# Chocolate_Vending_Machine_V2_1.net
KiCad netlist of a schematic drawn in Altium Designer
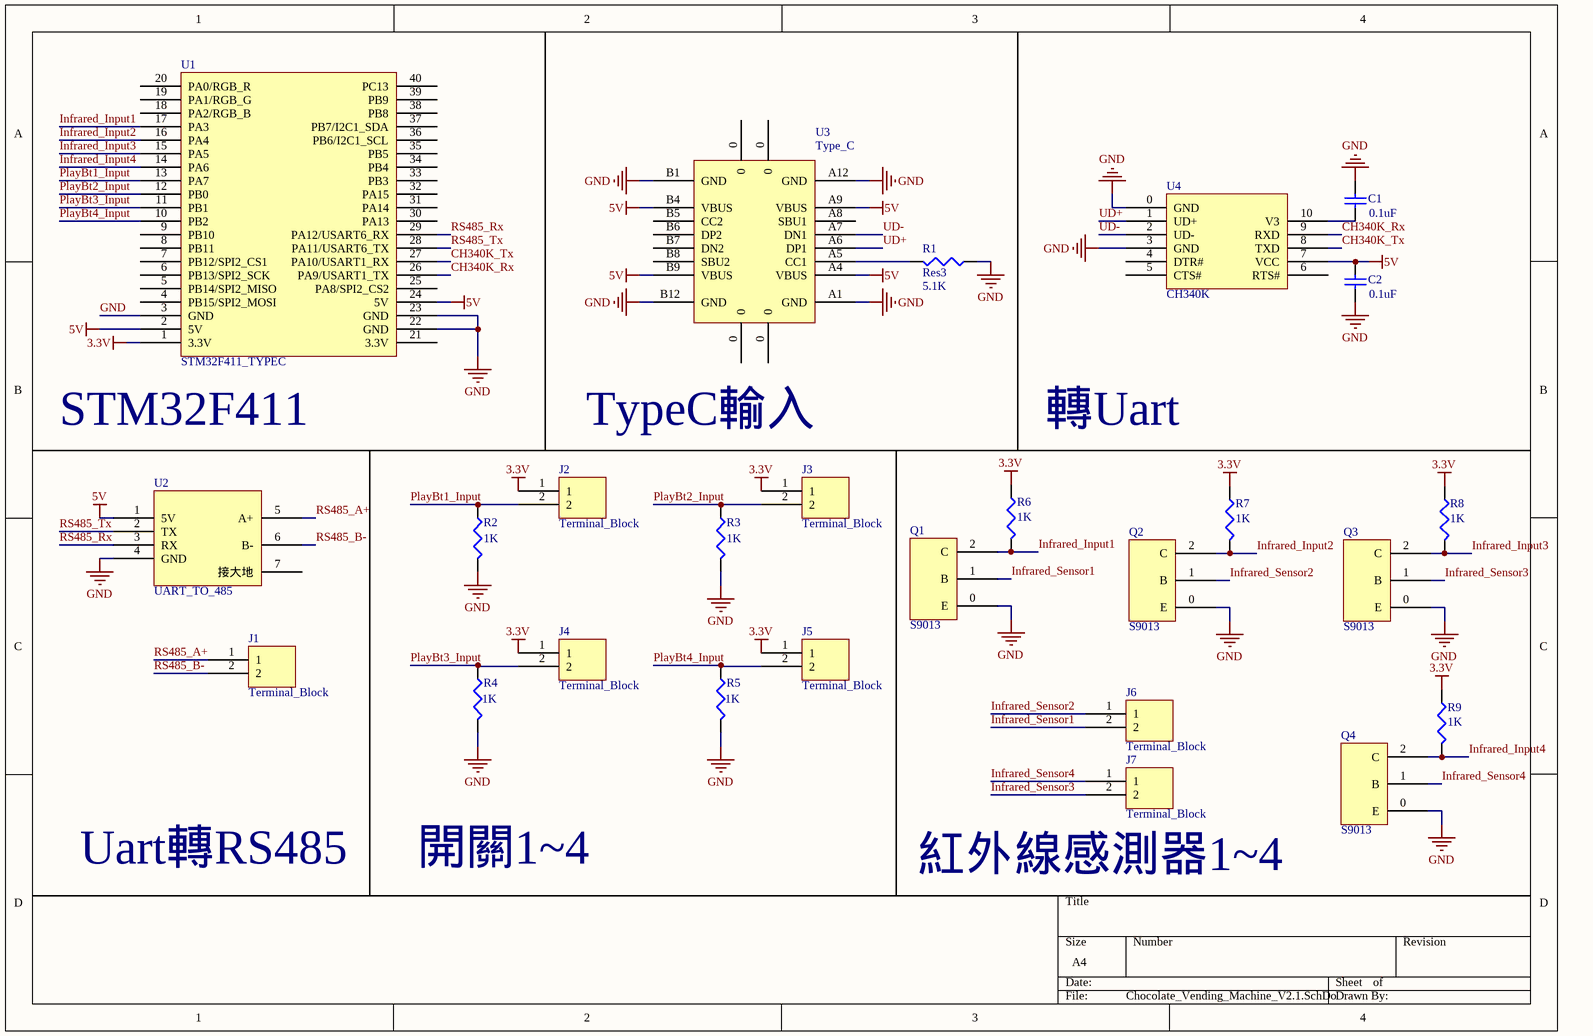
[diagram p0: Chocolate_Vending_Machine_V2.1.SchDoc]

(export (version "E")
  (design (tool "Eeschema 10.0.6"))
  (components
    (comp (ref "C1")
      (value "0.1uF")
      (footprint "1608[0603]")
      (description "Capacitor (Semiconductor SIM Model)")
      (fields (field (name "Comment") "Cap Semi") (field (name "PUBLISHER") "Altium Limited"))
      (libsource (lib "Miscellaneous Devices") (part "Cap Semi"))
    )
    (comp (ref "C2")
      (value "0.1uF")
      (footprint "1608[0603]")
      (description "Capacitor (Semiconductor SIM Model)")
      (fields (field (name "Comment") "Cap Semi") (field (name "PUBLISHER") "Altium Limited"))
      (libsource (lib "Miscellaneous Devices") (part "Cap Semi"))
    )
    (comp (ref "J1")
      (value "Terminal_Block")
      (footprint "terminal block")
      (libsource (lib "Lab_share") (part "Terminal Block"))
    )
    (comp (ref "J2")
      (value "Terminal_Block")
      (footprint "terminal block")
      (libsource (lib "Lab_share") (part "Terminal Block"))
    )
    (comp (ref "J3")
      (value "Terminal_Block")
      (footprint "terminal block")
      (libsource (lib "Lab_share") (part "Terminal Block"))
    )
    (comp (ref "J4")
      (value "Terminal_Block")
      (footprint "terminal block")
      (libsource (lib "Lab_share") (part "Terminal Block"))
    )
    (comp (ref "J5")
      (value "Terminal_Block")
      (footprint "terminal block")
      (libsource (lib "Lab_share") (part "Terminal Block"))
    )
    (comp (ref "J6")
      (value "Terminal_Block")
      (footprint "terminal block")
      (libsource (lib "Lab_share") (part "Terminal Block"))
    )
    (comp (ref "J7")
      (value "Terminal_Block")
      (footprint "terminal block")
      (libsource (lib "Lab_share") (part "Terminal Block"))
    )
    (comp (ref "Q1") (value "S9013") (footprint "S9013") (libsource (lib "Lab_share") (part "S9013")))
    (comp (ref "Q2") (value "S9013") (footprint "S9013") (libsource (lib "Lab_share") (part "S9013")))
    (comp (ref "Q3") (value "S9013") (footprint "S9013") (libsource (lib "Lab_share") (part "S9013")))
    (comp (ref "Q4") (value "S9013") (footprint "S9013") (libsource (lib "Lab_share") (part "S9013")))
    (comp (ref "R1")
      (value "Res3")
      (footprint "J1-0603")
      (description "Resistor")
      (fields (field (name "ALTIUM_VALUE") "5.1K") (field (name "PUBLISHER") "Altium Limited"))
      (libsource (lib "Miscellaneous Devices") (part "Res3"))
    )
    (comp (ref "R2")
      (value "1K")
      (footprint "J1-0603")
      (description "Resistor")
      (fields (field (name "Comment") "Res3") (field (name "PUBLISHER") "Altium Limited"))
      (libsource (lib "Miscellaneous Devices") (part "Res3"))
    )
    (comp (ref "R3")
      (value "1K")
      (footprint "J1-0603")
      (description "Resistor")
      (fields (field (name "Comment") "Res3") (field (name "PUBLISHER") "Altium Limited"))
      (libsource (lib "Miscellaneous Devices") (part "Res3"))
    )
    (comp (ref "R4")
      (value "1K")
      (footprint "J1-0603")
      (description "Resistor")
      (fields (field (name "Comment") "Res3") (field (name "PUBLISHER") "Altium Limited"))
      (libsource (lib "Miscellaneous Devices") (part "Res3"))
    )
    (comp (ref "R5")
      (value "1K")
      (footprint "J1-0603")
      (description "Resistor")
      (fields (field (name "Comment") "Res3") (field (name "PUBLISHER") "Altium Limited"))
      (libsource (lib "Miscellaneous Devices") (part "Res3"))
    )
    (comp (ref "R6")
      (value "1K")
      (footprint "J1-0603")
      (description "Resistor")
      (fields (field (name "Comment") "Res3") (field (name "PUBLISHER") "Altium Limited"))
      (libsource (lib "Miscellaneous Devices") (part "Res3"))
    )
    (comp (ref "R7")
      (value "1K")
      (footprint "J1-0603")
      (description "Resistor")
      (fields (field (name "Comment") "Res3") (field (name "PUBLISHER") "Altium Limited"))
      (libsource (lib "Miscellaneous Devices") (part "Res3"))
    )
    (comp (ref "R8")
      (value "1K")
      (footprint "J1-0603")
      (description "Resistor")
      (fields (field (name "Comment") "Res3") (field (name "PUBLISHER") "Altium Limited"))
      (libsource (lib "Miscellaneous Devices") (part "Res3"))
    )
    (comp (ref "R9")
      (value "1K")
      (footprint "J1-0603")
      (description "Resistor")
      (fields (field (name "Comment") "Res3") (field (name "PUBLISHER") "Altium Limited"))
      (libsource (lib "Miscellaneous Devices") (part "Res3"))
    )
    (comp (ref "U1")
      (value "STM32F411_TYPEC")
      (footprint "STM32F411_TypeC")
      (libsource (lib "Lab_share") (part "STM32F411_TYPEC"))
    )
    (comp (ref "U2")
      (value "UART_TO_485")
      (footprint "UART_TO_RS485")
      (libsource (lib "Lab_share") (part "UART_TO_485"))
    )
    (comp (ref "U3") (value "Type_C") (footprint "Type_C_V2") (libsource (lib "Lab_share") (part "Type_C")))
    (comp (ref "U4") (value "CH340K") (footprint "CH340K_V1") (libsource (lib "Lab_share") (part "CH340K")))
  )
  (nets
    (net (code "1") (name "/CH340K_Rx") (class "Default")
      (node (ref "U1") (pin "26") (pinfunction "PA9/USART1_TX_26") (pintype "passive"))
      (node (ref "U4") (pin "9") (pinfunction "RXD_9") (pintype "passive"))
    )
    (net (code "2") (name "/CH340K_Tx") (class "Default")
      (node (ref "U1") (pin "27") (pinfunction "PA10/USART1_RX_27") (pintype "passive"))
      (node (ref "U4") (pin "8") (pinfunction "TXD_8") (pintype "passive"))
    )
    (net (code "3") (name "/Infrared_Input1") (class "Default")
      (node (ref "Q1") (pin "2") (pinfunction "C_2") (pintype "passive"))
      (node (ref "R6") (pin "2") (pinfunction "2_2") (pintype "passive"))
      (node (ref "U1") (pin "17") (pinfunction "PA3_17") (pintype "passive"))
    )
    (net (code "4") (name "/Infrared_Input2") (class "Default")
      (node (ref "Q2") (pin "2") (pinfunction "C_2") (pintype "passive"))
      (node (ref "R7") (pin "2") (pinfunction "2_2") (pintype "passive"))
      (node (ref "U1") (pin "16") (pinfunction "PA4_16") (pintype "passive"))
    )
    (net (code "5") (name "/Infrared_Input3") (class "Default")
      (node (ref "Q3") (pin "2") (pinfunction "C_2") (pintype "passive"))
      (node (ref "R8") (pin "2") (pinfunction "2_2") (pintype "passive"))
      (node (ref "U1") (pin "15") (pinfunction "PA5_15") (pintype "passive"))
    )
    (net (code "6") (name "/Infrared_Input4") (class "Default")
      (node (ref "Q4") (pin "2") (pinfunction "C_2") (pintype "passive"))
      (node (ref "R9") (pin "2") (pinfunction "2_2") (pintype "passive"))
      (node (ref "U1") (pin "14") (pinfunction "PA6_14") (pintype "passive"))
    )
    (net (code "7") (name "/Infrared_Sensor1") (class "Default")
      (node (ref "J6") (pin "2") (pinfunction "2_2") (pintype "passive"))
      (node (ref "Q1") (pin "1") (pinfunction "B_1") (pintype "passive"))
    )
    (net (code "8") (name "/Infrared_Sensor2") (class "Default")
      (node (ref "J6") (pin "1") (pinfunction "1_1") (pintype "passive"))
      (node (ref "Q2") (pin "1") (pinfunction "B_1") (pintype "passive"))
    )
    (net (code "9") (name "/Infrared_Sensor3") (class "Default")
      (node (ref "J7") (pin "2") (pinfunction "2_2") (pintype "passive"))
      (node (ref "Q3") (pin "1") (pinfunction "B_1") (pintype "passive"))
    )
    (net (code "10") (name "/Infrared_Sensor4") (class "Default")
      (node (ref "J7") (pin "1") (pinfunction "1_1") (pintype "passive"))
      (node (ref "Q4") (pin "1") (pinfunction "B_1") (pintype "passive"))
    )
    (net (code "11") (name "/PlayBt1_Input") (class "Default")
      (node (ref "J2") (pin "2") (pinfunction "2_2") (pintype "passive"))
      (node (ref "R2") (pin "1") (pinfunction "1_1") (pintype "passive"))
      (node (ref "U1") (pin "13") (pinfunction "PA7_13") (pintype "passive"))
    )
    (net (code "12") (name "/PlayBt2_Input") (class "Default")
      (node (ref "J3") (pin "2") (pinfunction "2_2") (pintype "passive"))
      (node (ref "R3") (pin "1") (pinfunction "1_1") (pintype "passive"))
      (node (ref "U1") (pin "12") (pinfunction "PB0_12") (pintype "passive"))
    )
    (net (code "13") (name "/PlayBt3_Input") (class "Default")
      (node (ref "J4") (pin "2") (pinfunction "2_2") (pintype "passive"))
      (node (ref "R4") (pin "1") (pinfunction "1_1") (pintype "passive"))
      (node (ref "U1") (pin "11") (pinfunction "PB1_11") (pintype "passive"))
    )
    (net (code "14") (name "/PlayBt4_Input") (class "Default")
      (node (ref "J5") (pin "2") (pinfunction "2_2") (pintype "passive"))
      (node (ref "R5") (pin "1") (pinfunction "1_1") (pintype "passive"))
      (node (ref "U1") (pin "10") (pinfunction "PB2_10") (pintype "passive"))
    )
    (net (code "15") (name "/RS485_A+") (class "Default")
      (node (ref "J1") (pin "1") (pinfunction "1_1") (pintype "passive"))
      (node (ref "U2") (pin "5") (pinfunction "A+_5") (pintype "passive"))
    )
    (net (code "16") (name "/RS485_B-") (class "Default")
      (node (ref "J1") (pin "2") (pinfunction "2_2") (pintype "passive"))
      (node (ref "U2") (pin "6") (pinfunction "B-_6") (pintype "passive"))
    )
    (net (code "17") (name "/RS485_Rx") (class "Default")
      (node (ref "U1") (pin "29") (pinfunction "PA12/USART6_RX_29") (pintype "passive"))
      (node (ref "U2") (pin "3") (pinfunction "RX_3") (pintype "passive"))
    )
    (net (code "18") (name "/RS485_Tx") (class "Default")
      (node (ref "U1") (pin "28") (pinfunction "PA11/USART6_TX_28") (pintype "passive"))
      (node (ref "U2") (pin "2") (pinfunction "TX_2") (pintype "passive"))
    )
    (net (code "19") (name "/UD+") (class "Default")
      (node (ref "U3") (pin "A6") (pinfunction "DP1_A6") (pintype "passive"))
      (node (ref "U4") (pin "1") (pinfunction "UD+_1") (pintype "passive"))
    )
    (net (code "20") (name "/UD-") (class "Default")
      (node (ref "U3") (pin "A7") (pinfunction "DN1_A7") (pintype "passive"))
      (node (ref "U4") (pin "2") (pinfunction "UD-_2") (pintype "passive"))
    )
    (net (code "21") (name "3.3V") (class "Default")
      (node (ref "J2") (pin "1") (pinfunction "1_1") (pintype "passive"))
      (node (ref "J3") (pin "1") (pinfunction "1_1") (pintype "passive"))
      (node (ref "J4") (pin "1") (pinfunction "1_1") (pintype "passive"))
      (node (ref "J5") (pin "1") (pinfunction "1_1") (pintype "passive"))
      (node (ref "R6") (pin "1") (pinfunction "1_1") (pintype "passive"))
      (node (ref "R7") (pin "1") (pinfunction "1_1") (pintype "passive"))
      (node (ref "R8") (pin "1") (pinfunction "1_1") (pintype "passive"))
      (node (ref "R9") (pin "1") (pinfunction "1_1") (pintype "passive"))
      (node (ref "U1") (pin "1") (pinfunction "3.3V_1") (pintype "passive"))
    )
    (net (code "22") (name "5V") (class "Default")
      (node (ref "C2") (pin "2") (pinfunction "2_2") (pintype "passive"))
      (node (ref "U1") (pin "2") (pinfunction "5V_2") (pintype "passive"))
      (node (ref "U1") (pin "24") (pinfunction "5V_24") (pintype "passive"))
      (node (ref "U2") (pin "1") (pinfunction "5V_1") (pintype "passive"))
      (node (ref "U3") (pin "A4") (pinfunction "VBUS_A4") (pintype "passive"))
      (node (ref "U3") (pin "A9") (pinfunction "VBUS_A9") (pintype "passive"))
      (node (ref "U3") (pin "B4") (pinfunction "VBUS_B4") (pintype "passive"))
      (node (ref "U3") (pin "B9") (pinfunction "VBUS_B9") (pintype "passive"))
      (node (ref "U4") (pin "7") (pinfunction "VCC_7") (pintype "passive"))
    )
    (net (code "23") (name "GND") (class "Default")
      (node (ref "C1") (pin "2") (pinfunction "2_2") (pintype "passive"))
      (node (ref "C2") (pin "1") (pinfunction "1_1") (pintype "passive"))
      (node (ref "Q1") (pin "0") (pinfunction "E_0") (pintype "passive"))
      (node (ref "Q2") (pin "0") (pinfunction "E_0") (pintype "passive"))
      (node (ref "Q3") (pin "0") (pinfunction "E_0") (pintype "passive"))
      (node (ref "Q4") (pin "0") (pinfunction "E_0") (pintype "passive"))
      (node (ref "R1") (pin "1") (pinfunction "1_1") (pintype "passive"))
      (node (ref "R2") (pin "2") (pinfunction "2_2") (pintype "passive"))
      (node (ref "R3") (pin "2") (pinfunction "2_2") (pintype "passive"))
      (node (ref "R4") (pin "2") (pinfunction "2_2") (pintype "passive"))
      (node (ref "R5") (pin "2") (pinfunction "2_2") (pintype "passive"))
      (node (ref "U1") (pin "22") (pinfunction "GND_22") (pintype "passive"))
      (node (ref "U1") (pin "23") (pinfunction "GND_23") (pintype "passive"))
      (node (ref "U1") (pin "3") (pinfunction "GND_3") (pintype "passive"))
      (node (ref "U2") (pin "4") (pinfunction "GND_4") (pintype "passive"))
      (node (ref "U3") (pin "A1") (pinfunction "GND_A1") (pintype "passive"))
      (node (ref "U3") (pin "A12") (pinfunction "GND_A12") (pintype "passive"))
      (node (ref "U3") (pin "B1") (pinfunction "GND_B1") (pintype "passive"))
      (node (ref "U3") (pin "B12") (pinfunction "GND_B12") (pintype "passive"))
      (node (ref "U4") (pin "0") (pinfunction "GND_0") (pintype "passive"))
      (node (ref "U4") (pin "3") (pinfunction "GND_3") (pintype "passive"))
    )
    (net (code "24") (name "Net-(U3-CC1)") (class "Default")
      (node (ref "R1") (pin "2") (pinfunction "2_2") (pintype "passive"))
      (node (ref "U3") (pin "A5") (pinfunction "CC1_A5") (pintype "passive"))
    )
    (net (code "25") (name "Net-(U4-V3)") (class "Default")
      (node (ref "C1") (pin "1") (pinfunction "1_1") (pintype "passive"))
      (node (ref "U4") (pin "10") (pinfunction "V3_10") (pintype "passive"))
    )
    (net (code "26") (name "unconnected-(U1-3.3V-Pad21)") (class "Default")
      (node (ref "U1") (pin "21") (pinfunction "3.3V_21") (pintype "passive"))
    )
    (net (code "27") (name "unconnected-(U1-PA0{slash}RGB_R-Pad20)") (class "Default")
      (node (ref "U1") (pin "20") (pinfunction "PA0/RGB_R_20") (pintype "passive"))
    )
    (net (code "28") (name "unconnected-(U1-PA1{slash}RGB_G-Pad19)") (class "Default")
      (node (ref "U1") (pin "19") (pinfunction "PA1/RGB_G_19") (pintype "passive"))
    )
    (net (code "29") (name "unconnected-(U1-PA2{slash}RGB_B-Pad18)") (class "Default")
      (node (ref "U1") (pin "18") (pinfunction "PA2/RGB_B_18") (pintype "passive"))
    )
    (net (code "30") (name "unconnected-(U1-PA8{slash}SPI2_CS2-Pad25)") (class "Default")
      (node (ref "U1") (pin "25") (pinfunction "PA8/SPI2_CS2_25") (pintype "passive"))
    )
    (net (code "31") (name "unconnected-(U1-PA13-Pad30)") (class "Default")
      (node (ref "U1") (pin "30") (pinfunction "PA13_30") (pintype "passive"))
    )
    (net (code "32") (name "unconnected-(U1-PA14-Pad31)") (class "Default")
      (node (ref "U1") (pin "31") (pinfunction "PA14_31") (pintype "passive"))
    )
    (net (code "33") (name "unconnected-(U1-PA15-Pad32)") (class "Default")
      (node (ref "U1") (pin "32") (pinfunction "PA15_32") (pintype "passive"))
    )
    (net (code "34") (name "unconnected-(U1-PB3-Pad33)") (class "Default")
      (node (ref "U1") (pin "33") (pinfunction "PB3_33") (pintype "passive"))
    )
    (net (code "35") (name "unconnected-(U1-PB4-Pad34)") (class "Default")
      (node (ref "U1") (pin "34") (pinfunction "PB4_34") (pintype "passive"))
    )
    (net (code "36") (name "unconnected-(U1-PB5-Pad35)") (class "Default")
      (node (ref "U1") (pin "35") (pinfunction "PB5_35") (pintype "passive"))
    )
    (net (code "37") (name "unconnected-(U1-PB6{slash}I2C1_SCL-Pad36)") (class "Default")
      (node (ref "U1") (pin "36") (pinfunction "PB6/I2C1_SCL_36") (pintype "passive"))
    )
    (net (code "38") (name "unconnected-(U1-PB7{slash}I2C1_SDA-Pad37)") (class "Default")
      (node (ref "U1") (pin "37") (pinfunction "PB7/I2C1_SDA_37") (pintype "passive"))
    )
    (net (code "39") (name "unconnected-(U1-PB8-Pad38)") (class "Default")
      (node (ref "U1") (pin "38") (pinfunction "PB8_38") (pintype "passive"))
    )
    (net (code "40") (name "unconnected-(U1-PB9-Pad39)") (class "Default")
      (node (ref "U1") (pin "39") (pinfunction "PB9_39") (pintype "passive"))
    )
    (net (code "41") (name "unconnected-(U1-PB10-Pad9)") (class "Default")
      (node (ref "U1") (pin "9") (pinfunction "PB10_9") (pintype "passive"))
    )
    (net (code "42") (name "unconnected-(U1-PB11-Pad8)") (class "Default")
      (node (ref "U1") (pin "8") (pinfunction "PB11_8") (pintype "passive"))
    )
    (net (code "43") (name "unconnected-(U1-PB12{slash}SPI2_CS1-Pad7)") (class "Default")
      (node (ref "U1") (pin "7") (pinfunction "PB12/SPI2_CS1_7") (pintype "passive"))
    )
    (net (code "44") (name "unconnected-(U1-PB13{slash}SPI2_SCK-Pad6)") (class "Default")
      (node (ref "U1") (pin "6") (pinfunction "PB13/SPI2_SCK_6") (pintype "passive"))
    )
    (net (code "45") (name "unconnected-(U1-PB14{slash}SPI2_MISO-Pad5)") (class "Default")
      (node (ref "U1") (pin "5") (pinfunction "PB14/SPI2_MISO_5") (pintype "passive"))
    )
    (net (code "46") (name "unconnected-(U1-PB15{slash}SPI2_MOSI-Pad4)") (class "Default")
      (node (ref "U1") (pin "4") (pinfunction "PB15/SPI2_MOSI_4") (pintype "passive"))
    )
    (net (code "47") (name "unconnected-(U1-PC13-Pad40)") (class "Default")
      (node (ref "U1") (pin "40") (pinfunction "PC13_40") (pintype "passive"))
    )
    (net (code "48") (name "unconnected-(U2-接大地-Pad7)") (class "Default")
      (node (ref "U2") (pin "7") (pinfunction "接大地_7") (pintype "passive"))
    )
    (net (code "49") (name "unconnected-(U3-CC2-PadB5)") (class "Default")
      (node (ref "U3") (pin "B5") (pinfunction "CC2_B5") (pintype "passive"))
    )
    (net (code "50") (name "unconnected-(U3-DN2-PadB7)") (class "Default")
      (node (ref "U3") (pin "B7") (pinfunction "DN2_B7") (pintype "passive"))
    )
    (net (code "51") (name "unconnected-(U3-DP2-PadB6)") (class "Default")
      (node (ref "U3") (pin "B6") (pinfunction "DP2_B6") (pintype "passive"))
    )
    (net (code "52") (name "unconnected-(U3-Pad0)") (class "Default")
      (node (ref "U3") (pin "0") (pinfunction "0_0") (pintype "passive"))
    )
    (net (code "53") (name "unconnected-(U3-Pad0)_1") (class "Default")
      (node (ref "U3") (pin "0") (pinfunction "0_0") (pintype "passive"))
    )
    (net (code "54") (name "unconnected-(U3-Pad0)_2") (class "Default")
      (node (ref "U3") (pin "0") (pinfunction "0_0") (pintype "passive"))
    )
    (net (code "55") (name "unconnected-(U3-Pad0)_3") (class "Default")
      (node (ref "U3") (pin "0") (pinfunction "0_0") (pintype "passive"))
    )
    (net (code "56") (name "unconnected-(U3-SBU1-PadA8)") (class "Default")
      (node (ref "U3") (pin "A8") (pinfunction "SBU1_A8") (pintype "passive"))
    )
    (net (code "57") (name "unconnected-(U3-SBU2-PadB8)") (class "Default")
      (node (ref "U3") (pin "B8") (pinfunction "SBU2_B8") (pintype "passive"))
    )
    (net (code "58") (name "unconnected-(U4-CTS#-Pad5)") (class "Default")
      (node (ref "U4") (pin "5") (pinfunction "CTS#_5") (pintype "passive"))
    )
    (net (code "59") (name "unconnected-(U4-DTR#-Pad4)") (class "Default")
      (node (ref "U4") (pin "4") (pinfunction "DTR#_4") (pintype "passive"))
    )
    (net (code "60") (name "unconnected-(U4-RTS#-Pad6)") (class "Default")
      (node (ref "U4") (pin "6") (pinfunction "RTS#_6") (pintype "passive"))
    )
  )
)
